# PA.net
KiCad netlist of a schematic drawn in Altium Designer
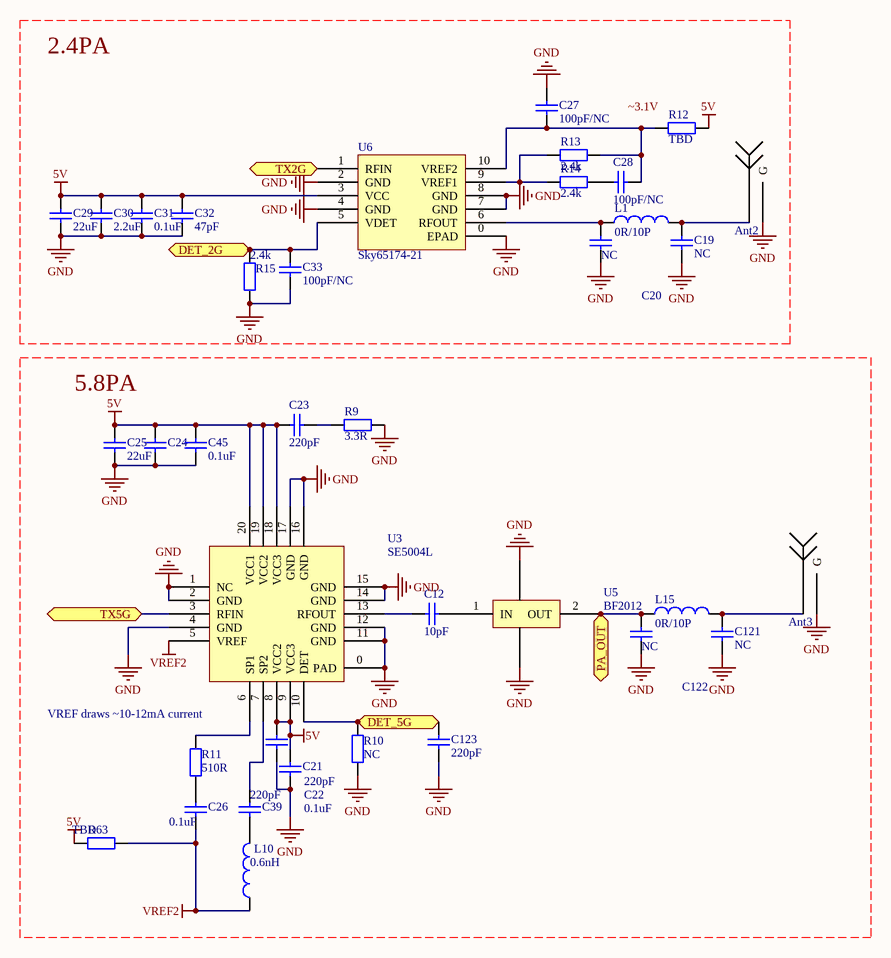
[diagram p0: PA.SchDoc]

(export (version "E")
  (design (tool "Eeschema 10.0.6"))
  (components
    (comp (ref "Ant2") (value "Antenna") (footprint "SMA-2") (libsource (lib "RTC6705") (part "Antenna")))
    (comp (ref "Ant3") (value "Antenna") (footprint "SMA-2") (libsource (lib "RTC6705") (part "Antenna")))
    (comp (ref "C12")
      (value "10pF")
      (footprint "0402")
      (description "Capacitor")
      (fields (field (name "Comment") "Cap") (field (name "PUBLISHER") "Altium Limited"))
      (libsource (lib "RTC6705") (part "Cap"))
    )
    (comp (ref "C19")
      (value "NC")
      (footprint "0402")
      (description "Capacitor")
      (fields (field (name "Comment") "Cap") (field (name "PUBLISHER") "Altium Limited"))
      (libsource (lib "RTC6705") (part "Cap"))
    )
    (comp (ref "C20")
      (value "NC")
      (footprint "0402")
      (description "Capacitor")
      (fields (field (name "Comment") "Cap") (field (name "PUBLISHER") "Altium Limited"))
      (libsource (lib "RTC6705") (part "Cap"))
    )
    (comp (ref "C21")
      (value "0.1uF")
      (footprint "0402")
      (description "Capacitor")
      (fields (field (name "Comment") "Cap") (field (name "PUBLISHER") "Altium Limited"))
      (libsource (lib "RTC6705") (part "Cap"))
    )
    (comp (ref "C22")
      (value "220pF")
      (footprint "0402")
      (description "Capacitor")
      (fields (field (name "Comment") "Cap") (field (name "PUBLISHER") "Altium Limited"))
      (libsource (lib "RTC6705") (part "Cap"))
    )
    (comp (ref "C23")
      (value "220pF")
      (footprint "0402")
      (description "Capacitor")
      (fields (field (name "Comment") "Cap") (field (name "PUBLISHER") "Altium Limited"))
      (libsource (lib "RTC6705") (part "Cap"))
    )
    (comp (ref "C24")
      (value "1uF")
      (footprint "0603")
      (description "Capacitor")
      (fields (field (name "PUBLISHER") "Altium Limited"))
      (libsource (lib "RTC6705") (part "Cap"))
    )
    (comp (ref "C25")
      (value "22uF")
      (footprint "0805")
      (description "Capacitor")
      (fields (field (name "Comment") "Cap") (field (name "PUBLISHER") "Altium Limited"))
      (libsource (lib "RTC6705") (part "Cap"))
    )
    (comp (ref "C26")
      (value "0.1uF")
      (footprint "0402")
      (description "Capacitor")
      (fields (field (name "Comment") "Cap") (field (name "PUBLISHER") "Altium Limited"))
      (libsource (lib "RTC6705") (part "Cap"))
    )
    (comp (ref "C27")
      (value "100pF/NC")
      (footprint "0402")
      (description "Capacitor")
      (fields (field (name "Comment") "Cap") (field (name "PUBLISHER") "Altium Limited"))
      (libsource (lib "RTC6705") (part "Cap"))
    )
    (comp (ref "C28")
      (value "100pF/NC")
      (footprint "0402")
      (description "Capacitor")
      (fields (field (name "Comment") "Cap") (field (name "PUBLISHER") "Altium Limited"))
      (libsource (lib "RTC6705") (part "Cap"))
    )
    (comp (ref "C29")
      (value "22uF")
      (footprint "0805")
      (description "Capacitor")
      (fields (field (name "Comment") "Cap") (field (name "PUBLISHER") "Altium Limited"))
      (libsource (lib "RTC6705") (part "Cap"))
    )
    (comp (ref "C30")
      (value "2.2uF")
      (footprint "0603")
      (description "Capacitor")
      (fields (field (name "Comment") "Cap") (field (name "PUBLISHER") "Altium Limited"))
      (libsource (lib "RTC6705") (part "Cap"))
    )
    (comp (ref "C31")
      (value "0.1uF")
      (footprint "0402")
      (description "Capacitor")
      (fields (field (name "Comment") "Cap") (field (name "PUBLISHER") "Altium Limited"))
      (libsource (lib "RTC6705") (part "Cap"))
    )
    (comp (ref "C32")
      (value "47pF")
      (footprint "0402")
      (description "Capacitor")
      (fields (field (name "Comment") "Cap") (field (name "PUBLISHER") "Altium Limited"))
      (libsource (lib "RTC6705") (part "Cap"))
    )
    (comp (ref "C33")
      (value "100pF/NC")
      (footprint "0402")
      (description "Capacitor")
      (fields (field (name "Comment") "Cap") (field (name "PUBLISHER") "Altium Limited"))
      (libsource (lib "RTC6705") (part "Cap"))
    )
    (comp (ref "C39")
      (value "220pF")
      (footprint "0402")
      (description "Capacitor")
      (fields (field (name "Comment") "Cap") (field (name "PUBLISHER") "Altium Limited"))
      (libsource (lib "RTC6705") (part "Cap"))
    )
    (comp (ref "C45")
      (value "0.1uF")
      (footprint "0402")
      (description "Capacitor")
      (fields (field (name "Comment") "Cap") (field (name "PUBLISHER") "Altium Limited"))
      (libsource (lib "RTC6705") (part "Cap"))
    )
    (comp (ref "C121")
      (value "NC")
      (footprint "0402")
      (description "Capacitor")
      (fields (field (name "Comment") "Cap") (field (name "PUBLISHER") "Altium Limited"))
      (libsource (lib "RTC6705") (part "Cap"))
    )
    (comp (ref "C122")
      (value "NC")
      (footprint "0402")
      (description "Capacitor")
      (fields (field (name "Comment") "Cap") (field (name "PUBLISHER") "Altium Limited"))
      (libsource (lib "RTC6705") (part "Cap"))
    )
    (comp (ref "C123")
      (value "220pF")
      (footprint "0402")
      (description "Capacitor")
      (fields (field (name "Comment") "Cap") (field (name "PUBLISHER") "Altium Limited"))
      (libsource (lib "RTC6705") (part "Cap"))
    )
    (comp (ref "L1")
      (value "0R/10P")
      (footprint "0402")
      (description "Inductor")
      (fields (field (name "PUBLISHER") "Altium Limited"))
      (libsource (lib "Miscellaneous Devices") (part "Inductor"))
    )
    (comp (ref "L10")
      (value "0.6nH")
      (footprint "0402")
      (description "Inductor")
      (fields (field (name "PUBLISHER") "Altium Limited"))
      (libsource (lib "Miscellaneous Devices") (part "Inductor"))
    )
    (comp (ref "L15")
      (value "0R/10P")
      (footprint "0402")
      (description "Inductor")
      (fields (field (name "PUBLISHER") "Altium Limited"))
      (libsource (lib "Miscellaneous Devices") (part "Inductor"))
    )
    (comp (ref "R9")
      (value "3.3R")
      (footprint "0402")
      (description "Resistor")
      (fields (field (name "Comment") "Res2") (field (name "PUBLISHER") "Altium Limited"))
      (libsource (lib "RTC6705") (part "Res2"))
    )
    (comp (ref "R10")
      (value "NC")
      (footprint "0402")
      (description "Resistor")
      (fields (field (name "Comment") "Res2") (field (name "PUBLISHER") "Altium Limited"))
      (libsource (lib "") (part "Res2_1"))
    )
    (comp (ref "R11")
      (value "510R")
      (footprint "0402")
      (description "Resistor")
      (fields (field (name "Comment") "Res2") (field (name "PUBLISHER") "Altium Limited"))
      (libsource (lib "") (part "Res2_1"))
    )
    (comp (ref "R12")
      (value "TBD")
      (footprint "0402")
      (description "Resistor")
      (fields (field (name "Comment") "Res2") (field (name "PUBLISHER") "Altium Limited"))
      (libsource (lib "RTC6705") (part "Res2"))
    )
    (comp (ref "R13")
      (value "2.4k")
      (footprint "0402")
      (description "Resistor")
      (fields (field (name "Comment") "Res2") (field (name "PUBLISHER") "Altium Limited"))
      (libsource (lib "RTC6705") (part "Res2"))
    )
    (comp (ref "R14")
      (value "2.4k")
      (footprint "0402")
      (description "Resistor")
      (fields (field (name "Comment") "Res2") (field (name "PUBLISHER") "Altium Limited"))
      (libsource (lib "RTC6705") (part "Res2"))
    )
    (comp (ref "R15")
      (value "2.4k")
      (footprint "0402")
      (description "Resistor")
      (fields (field (name "Comment") "Res2") (field (name "PUBLISHER") "Altium Limited"))
      (libsource (lib "") (part "Res2_1"))
    )
    (comp (ref "R63")
      (value "TBD")
      (footprint "0603")
      (description "Resistor")
      (fields (field (name "PUBLISHER") "Altium Limited"))
      (libsource (lib "RTC6705") (part "Res2"))
    )
    (comp (ref "U3") (value "SE5004L") (footprint "SE5004L") (libsource (lib "RTC6705") (part "SE5004L")))
    (comp (ref "U5") (value "BF2012") (footprint "LFB2H5") (libsource (lib "RTC6705") (part "BF2012")))
    (comp (ref "U6")
      (value "Sky65174-21")
      (footprint "SKY65174-21")
      (libsource (lib "WifiGain") (part "Sky65174-21"))
    )
  )
  (nets
    (net (code "1") (name "/DET_2G") (class "Default")
      (node (ref "C33") (pin "1") (pinfunction "1_1") (pintype "passive"))
      (node (ref "R15") (pin "2") (pinfunction "2_2") (pintype "passive"))
      (node (ref "U6") (pin "5") (pinfunction "VDET_5") (pintype "passive"))
    )
    (net (code "2") (name "/DET_5G") (class "Default")
      (node (ref "C123") (pin "1") (pinfunction "1_1") (pintype "passive"))
      (node (ref "R10") (pin "2") (pinfunction "2_2") (pintype "passive"))
      (node (ref "U3") (pin "10") (pinfunction "DET_10") (pintype "passive"))
    )
    (net (code "3") (name "/PA_OUT") (class "Default")
      (node (ref "C122") (pin "1") (pinfunction "1_1") (pintype "passive"))
      (node (ref "L15") (pin "1") (pinfunction "1_1") (pintype "passive"))
      (node (ref "U5") (pin "2") (pinfunction "OUT_2") (pintype "passive"))
    )
    (net (code "4") (name "/TX2G") (class "Default")
      (node (ref "U6") (pin "1") (pinfunction "RFIN_1") (pintype "passive"))
    )
    (net (code "5") (name "/TX5G") (class "Default")
      (node (ref "U3") (pin "3") (pinfunction "RFIN_3") (pintype "passive"))
    )
    (net (code "7") (name "5V") (class "Default")
      (node (ref "C21") (pin "2") (pinfunction "2_2") (pintype "passive"))
      (node (ref "C22") (pin "2") (pinfunction "2_2") (pintype "passive"))
      (node (ref "C23") (pin "2") (pinfunction "2_2") (pintype "passive"))
      (node (ref "C24") (pin "1") (pinfunction "1_1") (pintype "passive"))
      (node (ref "C25") (pin "2") (pinfunction "2_2") (pintype "passive"))
      (node (ref "C29") (pin "1") (pinfunction "1_1") (pintype "passive"))
      (node (ref "C30") (pin "1") (pinfunction "1_1") (pintype "passive"))
      (node (ref "C31") (pin "1") (pinfunction "1_1") (pintype "passive"))
      (node (ref "C32") (pin "1") (pinfunction "1_1") (pintype "passive"))
      (node (ref "C45") (pin "1") (pinfunction "1_1") (pintype "passive"))
      (node (ref "R12") (pin "1") (pinfunction "1_1") (pintype "passive"))
      (node (ref "R63") (pin "2") (pinfunction "2_2") (pintype "passive"))
      (node (ref "U3") (pin "18") (pinfunction "VCC3_18") (pintype "passive"))
      (node (ref "U3") (pin "19") (pinfunction "VCC2_19") (pintype "passive"))
      (node (ref "U3") (pin "20") (pinfunction "VCC1_20") (pintype "passive"))
      (node (ref "U3") (pin "8") (pinfunction "VCC2_8") (pintype "passive"))
      (node (ref "U3") (pin "9") (pinfunction "VCC3_9") (pintype "passive"))
      (node (ref "U6") (pin "3") (pinfunction "VCC_3") (pintype "passive"))
    )
    (net (code "8") (name "GND") (class "Default")
      (node (ref "Ant2") (pin "GND") (pinfunction "G_GND") (pintype "passive"))
      (node (ref "Ant3") (pin "GND") (pinfunction "G_GND") (pintype "passive"))
      (node (ref "C121") (pin "2") (pinfunction "2_2") (pintype "passive"))
      (node (ref "C122") (pin "2") (pinfunction "2_2") (pintype "passive"))
      (node (ref "C123") (pin "2") (pinfunction "2_2") (pintype "passive"))
      (node (ref "C19") (pin "2") (pinfunction "2_2") (pintype "passive"))
      (node (ref "C20") (pin "2") (pinfunction "2_2") (pintype "passive"))
      (node (ref "C21") (pin "1") (pinfunction "1_1") (pintype "passive"))
      (node (ref "C22") (pin "1") (pinfunction "1_1") (pintype "passive"))
      (node (ref "C24") (pin "2") (pinfunction "2_2") (pintype "passive"))
      (node (ref "C25") (pin "1") (pinfunction "1_1") (pintype "passive"))
      (node (ref "C27") (pin "1") (pinfunction "1_1") (pintype "passive"))
      (node (ref "C29") (pin "2") (pinfunction "2_2") (pintype "passive"))
      (node (ref "C30") (pin "2") (pinfunction "2_2") (pintype "passive"))
      (node (ref "C31") (pin "2") (pinfunction "2_2") (pintype "passive"))
      (node (ref "C32") (pin "2") (pinfunction "2_2") (pintype "passive"))
      (node (ref "C33") (pin "2") (pinfunction "2_2") (pintype "passive"))
      (node (ref "C45") (pin "2") (pinfunction "2_2") (pintype "passive"))
      (node (ref "R10") (pin "1") (pinfunction "1_1") (pintype "passive"))
      (node (ref "R15") (pin "1") (pinfunction "1_1") (pintype "passive"))
      (node (ref "R9") (pin "1") (pinfunction "1_1") (pintype "passive"))
      (node (ref "U3") (pin "0") (pinfunction "PAD_0") (pintype "passive"))
      (node (ref "U3") (pin "1") (pinfunction "NC_1") (pintype "passive"))
      (node (ref "U3") (pin "11") (pinfunction "GND_11") (pintype "passive"))
      (node (ref "U3") (pin "12") (pinfunction "GND_12") (pintype "passive"))
      (node (ref "U3") (pin "14") (pinfunction "GND_14") (pintype "passive"))
      (node (ref "U3") (pin "15") (pinfunction "GND_15") (pintype "passive"))
      (node (ref "U3") (pin "16") (pinfunction "GND_16") (pintype "passive"))
      (node (ref "U3") (pin "17") (pinfunction "GND_17") (pintype "passive"))
      (node (ref "U3") (pin "2") (pinfunction "GND_2") (pintype "passive"))
      (node (ref "U3") (pin "4") (pinfunction "GND_4") (pintype "passive"))
      (node (ref "U5") (pin "0") (pinfunction "GND_0") (pintype "passive"))
      (node (ref "U6") (pin "0") (pinfunction "EPAD_0") (pintype "passive"))
      (node (ref "U6") (pin "2") (pinfunction "GND_2") (pintype "passive"))
      (node (ref "U6") (pin "4") (pinfunction "GND_4") (pintype "passive"))
      (node (ref "U6") (pin "7") (pinfunction "GND_7") (pintype "passive"))
      (node (ref "U6") (pin "8") (pinfunction "GND_8") (pintype "passive"))
    )
    (net (code "9") (name "Net-(Ant2-Pad1)") (class "Default")
      (node (ref "Ant2") (pin "1") (pinfunction "1_1") (pintype "passive"))
      (node (ref "C19") (pin "1") (pinfunction "1_1") (pintype "passive"))
      (node (ref "L1") (pin "2") (pinfunction "2_2") (pintype "passive"))
    )
    (net (code "10") (name "Net-(Ant3-Pad1)") (class "Default")
      (node (ref "Ant3") (pin "1") (pinfunction "1_1") (pintype "passive"))
      (node (ref "C121") (pin "1") (pinfunction "1_1") (pintype "passive"))
      (node (ref "L15") (pin "2") (pinfunction "2_2") (pintype "passive"))
    )
    (net (code "11") (name "Net-(C23-Pad1)") (class "Default")
      (node (ref "C23") (pin "1") (pinfunction "1_1") (pintype "passive"))
      (node (ref "R9") (pin "2") (pinfunction "2_2") (pintype "passive"))
    )
    (net (code "12") (name "Net-(C26-Pad2)") (class "Default")
      (node (ref "C26") (pin "2") (pinfunction "2_2") (pintype "passive"))
      (node (ref "R11") (pin "1") (pinfunction "1_1") (pintype "passive"))
    )
    (net (code "13") (name "Net-(C28-Pad1)") (class "Default")
      (node (ref "C28") (pin "1") (pinfunction "1_1") (pintype "passive"))
      (node (ref "R14") (pin "1") (pinfunction "1_1") (pintype "passive"))
    )
    (net (code "14") (name "Net-(C39-Pad1)") (class "Default")
      (node (ref "C39") (pin "1") (pinfunction "1_1") (pintype "passive"))
      (node (ref "L10") (pin "2") (pinfunction "2_2") (pintype "passive"))
    )
    (net (code "15") (name "Net-(U3-RFOUT)") (class "Default")
      (node (ref "C12") (pin "1") (pinfunction "1_1") (pintype "passive"))
      (node (ref "U3") (pin "13") (pinfunction "RFOUT_13") (pintype "passive"))
    )
    (net (code "16") (name "Net-(U3-SP1)") (class "Default")
      (node (ref "R11") (pin "2") (pinfunction "2_2") (pintype "passive"))
      (node (ref "U3") (pin "6") (pinfunction "SP1_6") (pintype "passive"))
    )
    (net (code "17") (name "Net-(U3-SP2)") (class "Default")
      (node (ref "C39") (pin "2") (pinfunction "2_2") (pintype "passive"))
      (node (ref "U3") (pin "7") (pinfunction "SP2_7") (pintype "passive"))
    )
    (net (code "18") (name "Net-(U5-IN)") (class "Default")
      (node (ref "C12") (pin "2") (pinfunction "2_2") (pintype "passive"))
      (node (ref "U5") (pin "1") (pinfunction "IN_1") (pintype "passive"))
    )
    (net (code "19") (name "Net-(U6-RFOUT)") (class "Default")
      (node (ref "C20") (pin "1") (pinfunction "1_1") (pintype "passive"))
      (node (ref "L1") (pin "1") (pinfunction "1_1") (pintype "passive"))
      (node (ref "U6") (pin "6") (pinfunction "RFOUT_6") (pintype "passive"))
    )
    (net (code "20") (name "Net-(U6-VREF1)") (class "Default")
      (node (ref "R13") (pin "2") (pinfunction "2_2") (pintype "passive"))
      (node (ref "R14") (pin "2") (pinfunction "2_2") (pintype "passive"))
      (node (ref "U6") (pin "9") (pinfunction "VREF1_9") (pintype "passive"))
    )
    (net (code "21") (name "Net-(U6-VREF2)") (class "Default")
      (node (ref "C27") (pin "2") (pinfunction "2_2") (pintype "passive"))
      (node (ref "C28") (pin "2") (pinfunction "2_2") (pintype "passive"))
      (node (ref "R12") (pin "2") (pinfunction "2_2") (pintype "passive"))
      (node (ref "R13") (pin "1") (pinfunction "1_1") (pintype "passive"))
      (node (ref "U6") (pin "10") (pinfunction "VREF2_10") (pintype "passive"))
    )
    (net (code "22") (name "VREF2") (class "Default")
      (node (ref "C26") (pin "1") (pinfunction "1_1") (pintype "passive"))
      (node (ref "L10") (pin "1") (pinfunction "1_1") (pintype "passive"))
      (node (ref "R63") (pin "1") (pinfunction "1_1") (pintype "passive"))
      (node (ref "U3") (pin "5") (pinfunction "VREF_5") (pintype "passive"))
    )
  )
)
